# Isolator_Spi.net
KiCad netlist of a schematic drawn in Altium Designer
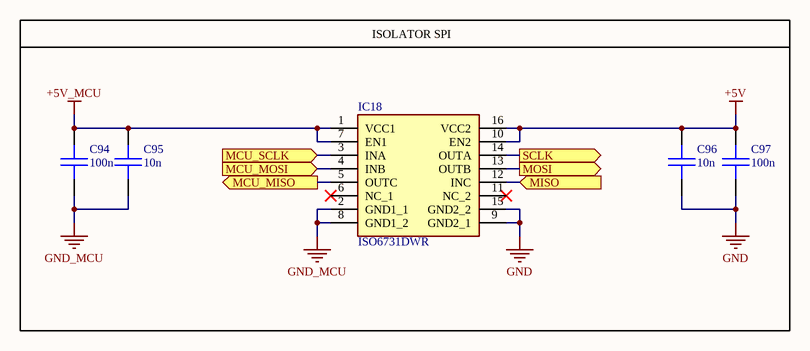
[diagram p0: Isolator_Spi.SchDoc]

(export (version "E")
  (design (tool "Eeschema 10.0.6"))
  (components
    (comp (ref "C94")
      (value "100n")
      (footprint "C_0603")
      (description "SMD Chip Capacitor")
      (libsource (lib "My_Integrated_Lib") (part "CAP"))
    )
    (comp (ref "C95")
      (value "10n")
      (footprint "C_0603")
      (description "SMD Chip Capacitor")
      (libsource (lib "My_Integrated_Lib") (part "CAP"))
    )
    (comp (ref "C96")
      (value "10n")
      (footprint "C_0603")
      (description "SMD Chip Capacitor")
      (libsource (lib "My_Integrated_Lib") (part "CAP"))
    )
    (comp (ref "C97")
      (value "100n")
      (footprint "C_0603")
      (description "SMD Chip Capacitor")
      (libsource (lib "My_Integrated_Lib") (part "CAP"))
    )
    (comp (ref "IC18")
      (value "ISO6731DWR")
      (footprint "SOIC127P1030X265-16N")
      (description "Integrated Circuit")
      (fields (field (name "MOUSER PART NUMBER") "595-ISO6731DWR"))
      (libsource (lib "My_Integrated_Lib") (part "ISO6731DWR"))
    )
  )
  (nets
    (net (code "1") (name "+5V") (class "Default")
      (node (ref "C96") (pin "2") (pinfunction "2_2") (pintype "passive"))
      (node (ref "C97") (pin "2") (pinfunction "2_2") (pintype "passive"))
      (node (ref "IC18") (pin "10") (pinfunction "EN2_10") (pintype "passive"))
      (node (ref "IC18") (pin "16") (pinfunction "VCC2_16") (pintype "passive"))
    )
    (net (code "2") (name "+5V_MCU") (class "Default")
      (node (ref "C94") (pin "2") (pinfunction "2_2") (pintype "passive"))
      (node (ref "C95") (pin "2") (pinfunction "2_2") (pintype "passive"))
      (node (ref "IC18") (pin "1") (pinfunction "VCC1_1") (pintype "passive"))
      (node (ref "IC18") (pin "7") (pinfunction "EN1_7") (pintype "passive"))
    )
    (net (code "3") (name "/MCU_MISO") (class "Default")
      (node (ref "IC18") (pin "5") (pinfunction "OUTC_5") (pintype "passive"))
    )
    (net (code "4") (name "/MCU_MOSI") (class "Default")
      (node (ref "IC18") (pin "4") (pinfunction "INB_4") (pintype "passive"))
    )
    (net (code "5") (name "/MCU_SCLK") (class "Default")
      (node (ref "IC18") (pin "3") (pinfunction "INA_3") (pintype "passive"))
    )
    (net (code "6") (name "/MISO") (class "Default")
      (node (ref "IC18") (pin "12") (pinfunction "INC_12") (pintype "passive"))
    )
    (net (code "7") (name "/MOSI") (class "Default")
      (node (ref "IC18") (pin "13") (pinfunction "OUTB_13") (pintype "passive"))
    )
    (net (code "8") (name "/SCLK") (class "Default")
      (node (ref "IC18") (pin "14") (pinfunction "OUTA_14") (pintype "passive"))
    )
    (net (code "9") (name "GND") (class "Default")
      (node (ref "C96") (pin "1") (pinfunction "1_1") (pintype "passive"))
      (node (ref "C97") (pin "1") (pinfunction "1_1") (pintype "passive"))
      (node (ref "IC18") (pin "15") (pinfunction "GND2_2_15") (pintype "passive"))
      (node (ref "IC18") (pin "9") (pinfunction "GND2_1_9") (pintype "passive"))
    )
    (net (code "10") (name "GND_MCU") (class "Default")
      (node (ref "C94") (pin "1") (pinfunction "1_1") (pintype "passive"))
      (node (ref "C95") (pin "1") (pinfunction "1_1") (pintype "passive"))
      (node (ref "IC18") (pin "2") (pinfunction "GND1_1_2") (pintype "passive"))
      (node (ref "IC18") (pin "8") (pinfunction "GND1_2_8") (pintype "passive"))
    )
    (net (code "11") (name "unconnected-(IC18-NC_1-Pad6)") (class "Default")
      (node (ref "IC18") (pin "6") (pinfunction "NC_1_6") (pintype "passive+no_connect"))
    )
    (net (code "12") (name "unconnected-(IC18-NC_2-Pad11)") (class "Default")
      (node (ref "IC18") (pin "11") (pinfunction "NC_2_11") (pintype "passive+no_connect"))
    )
  )
)
